# i2c_multiplexer_shield_v1.net
KiCad netlist of a schematic drawn in EAGLE
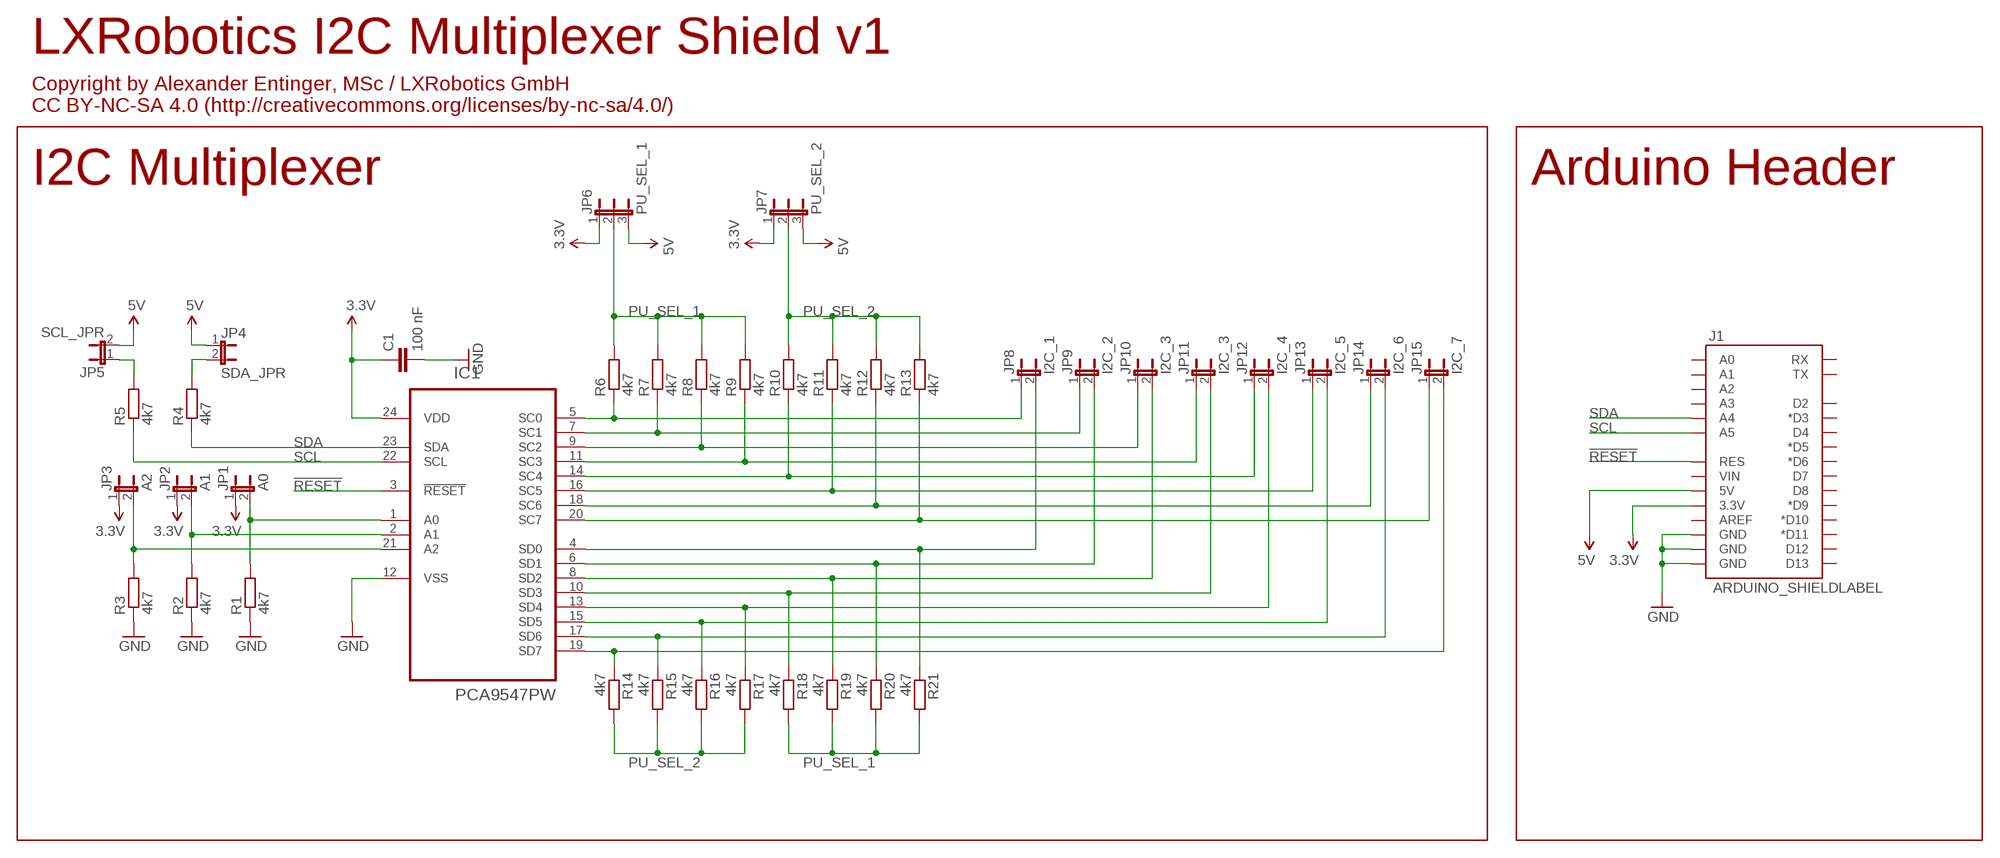
[diagram p0: schematic, sheet 1]

(export (version "E")
  (design (tool "Eeschema 10.0.6"))
  (components
    (comp (ref "C1")
      (value "100 nF")
      (footprint "eagle-import:C0805")
      (libsource (lib "eagle-import") (part "C-EUC0805"))
    )
    (comp (ref "IC1")
      (value "PCA9547PW")
      (footprint "eagle-import:SOP65P640X110-24N")
      (libsource (lib "eagle-import") (part "PCA9547PW"))
    )
    (comp (ref "J1")
      (value "ARDUINO_SHIELDLABEL")
      (footprint "eagle-import:DUEMILANOVE_SHIELD")
      (libsource (lib "eagle-import") (part "ARDUINO_SHIELDLABEL"))
    )
    (comp (ref "JP1")
      (value "A0")
      (footprint "eagle-import:JP1")
      (libsource (lib "eagle-import") (part "JP1E"))
    )
    (comp (ref "JP2")
      (value "A1")
      (footprint "eagle-import:JP1")
      (libsource (lib "eagle-import") (part "JP1E"))
    )
    (comp (ref "JP3")
      (value "A2")
      (footprint "eagle-import:JP1")
      (libsource (lib "eagle-import") (part "JP1E"))
    )
    (comp (ref "JP4")
      (value "SDA_JPR")
      (footprint "eagle-import:JP1")
      (libsource (lib "eagle-import") (part "JP1E"))
    )
    (comp (ref "JP5")
      (value "SCL_JPR")
      (footprint "eagle-import:JP1")
      (libsource (lib "eagle-import") (part "JP1E"))
    )
    (comp (ref "JP6")
      (value "PU_SEL_1")
      (footprint "eagle-import:JP2")
      (libsource (lib "eagle-import") (part "JP2E"))
    )
    (comp (ref "JP7")
      (value "PU_SEL_2")
      (footprint "eagle-import:JP2")
      (libsource (lib "eagle-import") (part "JP2E"))
    )
    (comp (ref "JP8")
      (value "I2C_1")
      (footprint "eagle-import:JP1")
      (libsource (lib "eagle-import") (part "JP1E"))
    )
    (comp (ref "JP9")
      (value "I2C_2")
      (footprint "eagle-import:JP1")
      (libsource (lib "eagle-import") (part "JP1E"))
    )
    (comp (ref "JP10")
      (value "I2C_3")
      (footprint "eagle-import:JP1")
      (libsource (lib "eagle-import") (part "JP1E"))
    )
    (comp (ref "JP11")
      (value "I2C_3")
      (footprint "eagle-import:JP1")
      (libsource (lib "eagle-import") (part "JP1E"))
    )
    (comp (ref "JP12")
      (value "I2C_4")
      (footprint "eagle-import:JP1")
      (libsource (lib "eagle-import") (part "JP1E"))
    )
    (comp (ref "JP13")
      (value "I2C_5")
      (footprint "eagle-import:JP1")
      (libsource (lib "eagle-import") (part "JP1E"))
    )
    (comp (ref "JP14")
      (value "I2C_6")
      (footprint "eagle-import:JP1")
      (libsource (lib "eagle-import") (part "JP1E"))
    )
    (comp (ref "JP15")
      (value "I2C_7")
      (footprint "eagle-import:JP1")
      (libsource (lib "eagle-import") (part "JP1E"))
    )
    (comp (ref "R1")
      (value "4k7")
      (footprint "eagle-import:R0805")
      (libsource (lib "eagle-import") (part "R-EU_R0805"))
    )
    (comp (ref "R2")
      (value "4k7")
      (footprint "eagle-import:R0805")
      (libsource (lib "eagle-import") (part "R-EU_R0805"))
    )
    (comp (ref "R3")
      (value "4k7")
      (footprint "eagle-import:R0805")
      (libsource (lib "eagle-import") (part "R-EU_R0805"))
    )
    (comp (ref "R4")
      (value "4k7")
      (footprint "eagle-import:R0805")
      (libsource (lib "eagle-import") (part "R-EU_R0805"))
    )
    (comp (ref "R5")
      (value "4k7")
      (footprint "eagle-import:R0805")
      (libsource (lib "eagle-import") (part "R-EU_R0805"))
    )
    (comp (ref "R6")
      (value "4k7")
      (footprint "eagle-import:R0805")
      (libsource (lib "eagle-import") (part "R-EU_R0805"))
    )
    (comp (ref "R7")
      (value "4k7")
      (footprint "eagle-import:R0805")
      (libsource (lib "eagle-import") (part "R-EU_R0805"))
    )
    (comp (ref "R8")
      (value "4k7")
      (footprint "eagle-import:R0805")
      (libsource (lib "eagle-import") (part "R-EU_R0805"))
    )
    (comp (ref "R9")
      (value "4k7")
      (footprint "eagle-import:R0805")
      (libsource (lib "eagle-import") (part "R-EU_R0805"))
    )
    (comp (ref "R10")
      (value "4k7")
      (footprint "eagle-import:R0805")
      (libsource (lib "eagle-import") (part "R-EU_R0805"))
    )
    (comp (ref "R11")
      (value "4k7")
      (footprint "eagle-import:R0805")
      (libsource (lib "eagle-import") (part "R-EU_R0805"))
    )
    (comp (ref "R12")
      (value "4k7")
      (footprint "eagle-import:R0805")
      (libsource (lib "eagle-import") (part "R-EU_R0805"))
    )
    (comp (ref "R13")
      (value "4k7")
      (footprint "eagle-import:R0805")
      (libsource (lib "eagle-import") (part "R-EU_R0805"))
    )
    (comp (ref "R14")
      (value "4k7")
      (footprint "eagle-import:R0805")
      (libsource (lib "eagle-import") (part "R-EU_R0805"))
    )
    (comp (ref "R15")
      (value "4k7")
      (footprint "eagle-import:R0805")
      (libsource (lib "eagle-import") (part "R-EU_R0805"))
    )
    (comp (ref "R16")
      (value "4k7")
      (footprint "eagle-import:R0805")
      (libsource (lib "eagle-import") (part "R-EU_R0805"))
    )
    (comp (ref "R17")
      (value "4k7")
      (footprint "eagle-import:R0805")
      (libsource (lib "eagle-import") (part "R-EU_R0805"))
    )
    (comp (ref "R18")
      (value "4k7")
      (footprint "eagle-import:R0805")
      (libsource (lib "eagle-import") (part "R-EU_R0805"))
    )
    (comp (ref "R19")
      (value "4k7")
      (footprint "eagle-import:R0805")
      (libsource (lib "eagle-import") (part "R-EU_R0805"))
    )
    (comp (ref "R20")
      (value "4k7")
      (footprint "eagle-import:R0805")
      (libsource (lib "eagle-import") (part "R-EU_R0805"))
    )
    (comp (ref "R21")
      (value "4k7")
      (footprint "eagle-import:R0805")
      (libsource (lib "eagle-import") (part "R-EU_R0805"))
    )
  )
  (nets
    (net (code "1") (name "/PU_SEL_1") (class "Default")
      (node (ref "JP6") (pin "2") (pinfunction "2_2") (pintype "passive"))
      (node (ref "R18") (pin "2") (pinfunction "2_2") (pintype "passive"))
      (node (ref "R19") (pin "2") (pinfunction "2_2") (pintype "passive"))
      (node (ref "R20") (pin "2") (pinfunction "2_2") (pintype "passive"))
      (node (ref "R21") (pin "2") (pinfunction "2_2") (pintype "passive"))
      (node (ref "R6") (pin "2") (pinfunction "2_2") (pintype "passive"))
      (node (ref "R7") (pin "2") (pinfunction "2_2") (pintype "passive"))
      (node (ref "R8") (pin "2") (pinfunction "2_2") (pintype "passive"))
      (node (ref "R9") (pin "2") (pinfunction "2_2") (pintype "passive"))
    )
    (net (code "2") (name "/PU_SEL_2") (class "Default")
      (node (ref "JP7") (pin "2") (pinfunction "2_2") (pintype "passive"))
      (node (ref "R10") (pin "2") (pinfunction "2_2") (pintype "passive"))
      (node (ref "R11") (pin "2") (pinfunction "2_2") (pintype "passive"))
      (node (ref "R12") (pin "2") (pinfunction "2_2") (pintype "passive"))
      (node (ref "R13") (pin "2") (pinfunction "2_2") (pintype "passive"))
      (node (ref "R14") (pin "2") (pinfunction "2_2") (pintype "passive"))
      (node (ref "R15") (pin "2") (pinfunction "2_2") (pintype "passive"))
      (node (ref "R16") (pin "2") (pinfunction "2_2") (pintype "passive"))
      (node (ref "R17") (pin "2") (pinfunction "2_2") (pintype "passive"))
    )
    (net (code "3") (name "/SCL") (class "Default")
      (node (ref "IC1") (pin "22") (pinfunction "SCL_22") (pintype "input"))
      (node (ref "J1") (pin "A5") (pinfunction "A5_A5") (pintype "bidirectional"))
      (node (ref "R5") (pin "1") (pinfunction "1_1") (pintype "passive"))
    )
    (net (code "4") (name "/SDA") (class "Default")
      (node (ref "IC1") (pin "23") (pinfunction "SDA_23") (pintype "bidirectional"))
      (node (ref "J1") (pin "A4") (pinfunction "A4_A4") (pintype "bidirectional"))
      (node (ref "R4") (pin "1") (pinfunction "1_1") (pintype "passive"))
    )
    (net (code "5") (name "/~{RESET}") (class "Default")
      (node (ref "IC1") (pin "3") (pinfunction "~{RESET}_3") (pintype "input"))
      (node (ref "J1") (pin "RES") (pinfunction "RES_RES") (pintype "bidirectional"))
    )
    (net (code "6") (name "3.3V") (class "Default")
      (node (ref "C1") (pin "1") (pinfunction "1_1") (pintype "passive"))
      (node (ref "IC1") (pin "24") (pinfunction "VDD_24") (pintype "power_in"))
      (node (ref "J1") (pin "3.3V") (pinfunction "3.3V_3.3V") (pintype "bidirectional"))
      (node (ref "JP1") (pin "1") (pinfunction "1_1") (pintype "passive"))
      (node (ref "JP2") (pin "1") (pinfunction "1_1") (pintype "passive"))
      (node (ref "JP3") (pin "1") (pinfunction "1_1") (pintype "passive"))
      (node (ref "JP6") (pin "1") (pinfunction "1_1") (pintype "passive"))
      (node (ref "JP7") (pin "1") (pinfunction "1_1") (pintype "passive"))
    )
    (net (code "7") (name "5V") (class "Default")
      (node (ref "J1") (pin "5V") (pinfunction "5V_5V") (pintype "bidirectional"))
      (node (ref "JP4") (pin "1") (pinfunction "1_1") (pintype "passive"))
      (node (ref "JP5") (pin "2") (pinfunction "2_2") (pintype "passive"))
      (node (ref "JP6") (pin "3") (pinfunction "3_3") (pintype "passive"))
      (node (ref "JP7") (pin "3") (pinfunction "3_3") (pintype "passive"))
    )
    (net (code "8") (name "GND") (class "Default")
      (node (ref "C1") (pin "2") (pinfunction "2_2") (pintype "passive"))
      (node (ref "IC1") (pin "12") (pinfunction "VSS_12") (pintype "passive"))
      (node (ref "J1") (pin "GND@0") (pinfunction "GND_GND@0") (pintype "bidirectional"))
      (node (ref "J1") (pin "GND@1") (pinfunction "GND_GND@1") (pintype "bidirectional"))
      (node (ref "J1") (pin "GND@2") (pinfunction "GND_GND@2") (pintype "bidirectional"))
      (node (ref "R1") (pin "1") (pinfunction "1_1") (pintype "passive"))
      (node (ref "R2") (pin "1") (pinfunction "1_1") (pintype "passive"))
      (node (ref "R3") (pin "1") (pinfunction "1_1") (pintype "passive"))
    )
    (net (code "9") (name "Net-(IC1-A0)") (class "Default")
      (node (ref "IC1") (pin "1") (pinfunction "A0_1") (pintype "input"))
      (node (ref "JP1") (pin "2") (pinfunction "2_2") (pintype "passive"))
      (node (ref "R1") (pin "2") (pinfunction "2_2") (pintype "passive"))
    )
    (net (code "10") (name "Net-(IC1-A1)") (class "Default")
      (node (ref "IC1") (pin "2") (pinfunction "A1_2") (pintype "input"))
      (node (ref "JP2") (pin "2") (pinfunction "2_2") (pintype "passive"))
      (node (ref "R2") (pin "2") (pinfunction "2_2") (pintype "passive"))
    )
    (net (code "11") (name "Net-(IC1-A2)") (class "Default")
      (node (ref "IC1") (pin "21") (pinfunction "A2_21") (pintype "input"))
      (node (ref "JP3") (pin "2") (pinfunction "2_2") (pintype "passive"))
      (node (ref "R3") (pin "2") (pinfunction "2_2") (pintype "passive"))
    )
    (net (code "12") (name "Net-(IC1-SC0)") (class "Default")
      (node (ref "IC1") (pin "5") (pinfunction "SC0_5") (pintype "output"))
      (node (ref "JP8") (pin "1") (pinfunction "1_1") (pintype "passive"))
      (node (ref "R6") (pin "1") (pinfunction "1_1") (pintype "passive"))
    )
    (net (code "13") (name "Net-(IC1-SC1)") (class "Default")
      (node (ref "IC1") (pin "7") (pinfunction "SC1_7") (pintype "output"))
      (node (ref "JP9") (pin "1") (pinfunction "1_1") (pintype "passive"))
      (node (ref "R7") (pin "1") (pinfunction "1_1") (pintype "passive"))
    )
    (net (code "14") (name "Net-(IC1-SC2)") (class "Default")
      (node (ref "IC1") (pin "9") (pinfunction "SC2_9") (pintype "output"))
      (node (ref "JP10") (pin "1") (pinfunction "1_1") (pintype "passive"))
      (node (ref "R8") (pin "1") (pinfunction "1_1") (pintype "passive"))
    )
    (net (code "15") (name "Net-(IC1-SC3)") (class "Default")
      (node (ref "IC1") (pin "11") (pinfunction "SC3_11") (pintype "output"))
      (node (ref "JP11") (pin "1") (pinfunction "1_1") (pintype "passive"))
      (node (ref "R9") (pin "1") (pinfunction "1_1") (pintype "passive"))
    )
    (net (code "16") (name "Net-(IC1-SC4)") (class "Default")
      (node (ref "IC1") (pin "14") (pinfunction "SC4_14") (pintype "output"))
      (node (ref "JP12") (pin "1") (pinfunction "1_1") (pintype "passive"))
      (node (ref "R10") (pin "1") (pinfunction "1_1") (pintype "passive"))
    )
    (net (code "17") (name "Net-(IC1-SC5)") (class "Default")
      (node (ref "IC1") (pin "16") (pinfunction "SC5_16") (pintype "output"))
      (node (ref "JP13") (pin "1") (pinfunction "1_1") (pintype "passive"))
      (node (ref "R11") (pin "1") (pinfunction "1_1") (pintype "passive"))
    )
    (net (code "18") (name "Net-(IC1-SC6)") (class "Default")
      (node (ref "IC1") (pin "18") (pinfunction "SC6_18") (pintype "output"))
      (node (ref "JP14") (pin "1") (pinfunction "1_1") (pintype "passive"))
      (node (ref "R12") (pin "1") (pinfunction "1_1") (pintype "passive"))
    )
    (net (code "19") (name "Net-(IC1-SC7)") (class "Default")
      (node (ref "IC1") (pin "20") (pinfunction "SC7_20") (pintype "output"))
      (node (ref "JP15") (pin "1") (pinfunction "1_1") (pintype "passive"))
      (node (ref "R13") (pin "1") (pinfunction "1_1") (pintype "passive"))
    )
    (net (code "20") (name "Net-(IC1-SD0)") (class "Default")
      (node (ref "IC1") (pin "4") (pinfunction "SD0_4") (pintype "output"))
      (node (ref "JP8") (pin "2") (pinfunction "2_2") (pintype "passive"))
      (node (ref "R21") (pin "1") (pinfunction "1_1") (pintype "passive"))
    )
    (net (code "21") (name "Net-(IC1-SD1)") (class "Default")
      (node (ref "IC1") (pin "6") (pinfunction "SD1_6") (pintype "output"))
      (node (ref "JP9") (pin "2") (pinfunction "2_2") (pintype "passive"))
      (node (ref "R20") (pin "1") (pinfunction "1_1") (pintype "passive"))
    )
    (net (code "22") (name "Net-(IC1-SD2)") (class "Default")
      (node (ref "IC1") (pin "8") (pinfunction "SD2_8") (pintype "output"))
      (node (ref "JP10") (pin "2") (pinfunction "2_2") (pintype "passive"))
      (node (ref "R19") (pin "1") (pinfunction "1_1") (pintype "passive"))
    )
    (net (code "23") (name "Net-(IC1-SD3)") (class "Default")
      (node (ref "IC1") (pin "10") (pinfunction "SD3_10") (pintype "output"))
      (node (ref "JP11") (pin "2") (pinfunction "2_2") (pintype "passive"))
      (node (ref "R18") (pin "1") (pinfunction "1_1") (pintype "passive"))
    )
    (net (code "24") (name "Net-(IC1-SD4)") (class "Default")
      (node (ref "IC1") (pin "13") (pinfunction "SD4_13") (pintype "output"))
      (node (ref "JP12") (pin "2") (pinfunction "2_2") (pintype "passive"))
      (node (ref "R17") (pin "1") (pinfunction "1_1") (pintype "passive"))
    )
    (net (code "25") (name "Net-(IC1-SD5)") (class "Default")
      (node (ref "IC1") (pin "15") (pinfunction "SD5_15") (pintype "output"))
      (node (ref "JP13") (pin "2") (pinfunction "2_2") (pintype "passive"))
      (node (ref "R16") (pin "1") (pinfunction "1_1") (pintype "passive"))
    )
    (net (code "26") (name "Net-(IC1-SD6)") (class "Default")
      (node (ref "IC1") (pin "17") (pinfunction "SD6_17") (pintype "output"))
      (node (ref "JP14") (pin "2") (pinfunction "2_2") (pintype "passive"))
      (node (ref "R15") (pin "1") (pinfunction "1_1") (pintype "passive"))
    )
    (net (code "27") (name "Net-(IC1-SD7)") (class "Default")
      (node (ref "IC1") (pin "19") (pinfunction "SD7_19") (pintype "output"))
      (node (ref "JP15") (pin "2") (pinfunction "2_2") (pintype "passive"))
      (node (ref "R14") (pin "1") (pinfunction "1_1") (pintype "passive"))
    )
    (net (code "28") (name "Net-(JP4-Pad2)") (class "Default")
      (node (ref "JP4") (pin "2") (pinfunction "2_2") (pintype "passive"))
      (node (ref "R4") (pin "2") (pinfunction "2_2") (pintype "passive"))
    )
    (net (code "29") (name "Net-(JP5-Pad1)") (class "Default")
      (node (ref "JP5") (pin "1") (pinfunction "1_1") (pintype "passive"))
      (node (ref "R5") (pin "2") (pinfunction "2_2") (pintype "passive"))
    )
    (net (code "30") (name "unconnected-(J1-*D3-PadD3)") (class "Default")
      (node (ref "J1") (pin "D3") (pinfunction "*D3_D3") (pintype "bidirectional"))
    )
    (net (code "31") (name "unconnected-(J1-*D5-PadD5)") (class "Default")
      (node (ref "J1") (pin "D5") (pinfunction "*D5_D5") (pintype "bidirectional"))
    )
    (net (code "32") (name "unconnected-(J1-*D6-PadD6)") (class "Default")
      (node (ref "J1") (pin "D6") (pinfunction "*D6_D6") (pintype "bidirectional"))
    )
    (net (code "33") (name "unconnected-(J1-*D9-PadD9)") (class "Default")
      (node (ref "J1") (pin "D9") (pinfunction "*D9_D9") (pintype "bidirectional"))
    )
    (net (code "34") (name "unconnected-(J1-*D10-PadD10)") (class "Default")
      (node (ref "J1") (pin "D10") (pinfunction "*D10_D10") (pintype "bidirectional"))
    )
    (net (code "35") (name "unconnected-(J1-*D11-PadD11)") (class "Default")
      (node (ref "J1") (pin "D11") (pinfunction "*D11_D11") (pintype "bidirectional"))
    )
    (net (code "36") (name "unconnected-(J1-PadA0)") (class "Default")
      (node (ref "J1") (pin "A0") (pinfunction "A0_A0") (pintype "bidirectional"))
    )
    (net (code "37") (name "unconnected-(J1-PadA1)") (class "Default")
      (node (ref "J1") (pin "A1") (pinfunction "A1_A1") (pintype "bidirectional"))
    )
    (net (code "38") (name "unconnected-(J1-PadA2)") (class "Default")
      (node (ref "J1") (pin "A2") (pinfunction "A2_A2") (pintype "bidirectional"))
    )
    (net (code "39") (name "unconnected-(J1-PadA3)") (class "Default")
      (node (ref "J1") (pin "A3") (pinfunction "A3_A3") (pintype "bidirectional"))
    )
    (net (code "40") (name "unconnected-(J1-PadAREF)") (class "Default")
      (node (ref "J1") (pin "AREF") (pinfunction "AREF_AREF") (pintype "bidirectional"))
    )
    (net (code "41") (name "unconnected-(J1-PadD2)") (class "Default")
      (node (ref "J1") (pin "D2") (pinfunction "D2_D2") (pintype "bidirectional"))
    )
    (net (code "42") (name "unconnected-(J1-PadD4)") (class "Default")
      (node (ref "J1") (pin "D4") (pinfunction "D4_D4") (pintype "bidirectional"))
    )
    (net (code "43") (name "unconnected-(J1-PadD7)") (class "Default")
      (node (ref "J1") (pin "D7") (pinfunction "D7_D7") (pintype "bidirectional"))
    )
    (net (code "44") (name "unconnected-(J1-PadD8)") (class "Default")
      (node (ref "J1") (pin "D8") (pinfunction "D8_D8") (pintype "bidirectional"))
    )
    (net (code "45") (name "unconnected-(J1-PadD12)") (class "Default")
      (node (ref "J1") (pin "D12") (pinfunction "D12_D12") (pintype "bidirectional"))
    )
    (net (code "46") (name "unconnected-(J1-PadD13)") (class "Default")
      (node (ref "J1") (pin "D13") (pinfunction "D13_D13") (pintype "bidirectional"))
    )
    (net (code "47") (name "unconnected-(J1-PadRX)") (class "Default")
      (node (ref "J1") (pin "RX") (pinfunction "RX_RX") (pintype "bidirectional"))
    )
    (net (code "48") (name "unconnected-(J1-PadTX)") (class "Default")
      (node (ref "J1") (pin "TX") (pinfunction "TX_TX") (pintype "bidirectional"))
    )
    (net (code "49") (name "unconnected-(J1-PadVIN)") (class "Default")
      (node (ref "J1") (pin "VIN") (pinfunction "VIN_VIN") (pintype "bidirectional"))
    )
  )
)
